# SDcard.net
KiCad netlist of a schematic drawn in Altium Designer
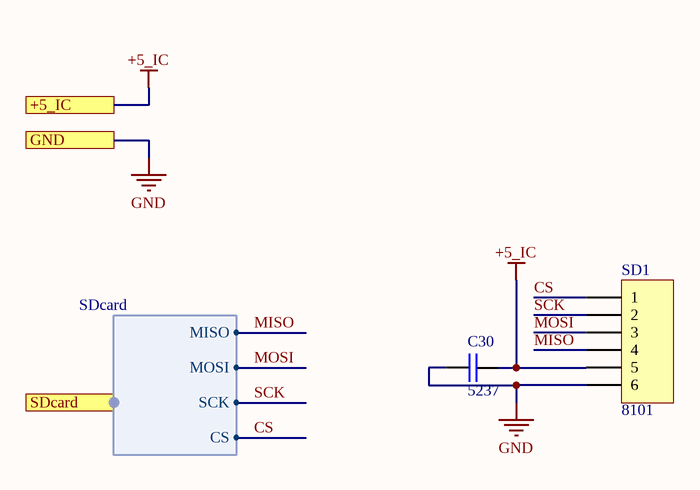
[diagram p0: SDcard.SchDoc]

(export (version "E")
  (design (tool "Eeschema 10.0.6"))
  (components
    (comp (ref "C30")
      (value "1u'F, 50'V")
      (footprint "CAP 1206/3216")
      (description "Bipolar ceramic capacitor SMD")
      (fields (field (name "INFLOW") "5237") (field (name "VALIDATION") "Valid"))
      (libsource (lib "aKaReZa") (part "Cap_Multi_1u_50_1206"))
    )
    (comp (ref "SD1")
      (value "6")
      (footprint "HDR_THT_6F_2.54mm")
      (description "Header, single row, 6 pin")
      (fields (field (name "INFLOW") "8101") (field (name "VALIDATION") "NT"))
      (libsource (lib "aKaReZa") (part "Con_FPH_6x1_V_THT_2.54"))
    )
  )
  (nets
    (net (code "2") (name "+5_IC") (class "Default")
      (node (ref "C30") (pin "2") (pinfunction "2_2") (pintype "passive"))
      (node (ref "SD1") (pin "5") (pinfunction "5_5") (pintype "passive"))
    )
    (net (code "3") (name "/CS") (class "Default")
      (node (ref "SD1") (pin "1") (pinfunction "1_1") (pintype "passive"))
    )
    (net (code "4") (name "/MISO") (class "Default")
      (node (ref "SD1") (pin "4") (pinfunction "4_4") (pintype "passive"))
    )
    (net (code "5") (name "/MOSI") (class "Default")
      (node (ref "SD1") (pin "3") (pinfunction "3_3") (pintype "passive"))
    )
    (net (code "6") (name "/SCK") (class "Default")
      (node (ref "SD1") (pin "2") (pinfunction "2_2") (pintype "passive"))
    )
    (net (code "8") (name "GND") (class "Default")
      (node (ref "C30") (pin "1") (pinfunction "1_1") (pintype "passive"))
      (node (ref "SD1") (pin "6") (pinfunction "6_6") (pintype "passive"))
    )
  )
)
